# SchemaAction.net
KiCad netlist of a schematic drawn in Altium Designer
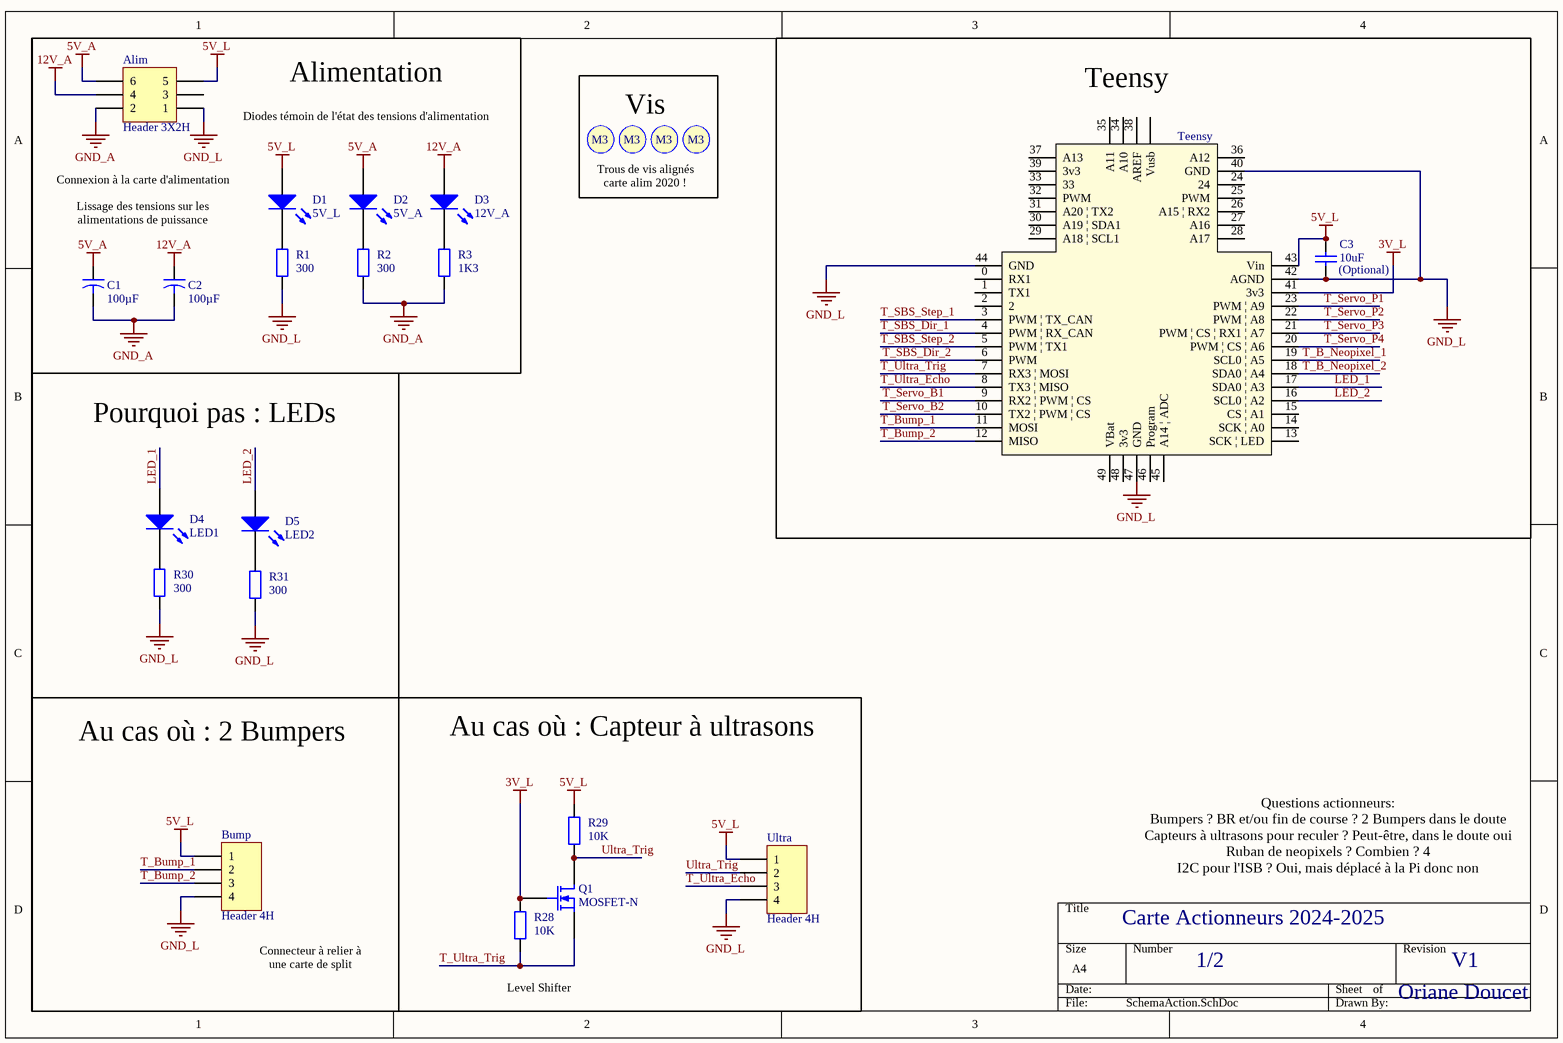
[diagram p0: SchemaAction.SchDoc]

(export (version "E")
  (design (tool "Eeschema 10.0.6"))
  (components
    (comp (ref "Alim")
      (value "Header 3X2H")
      (footprint "MOLEX_MINIFITJR_3X2")
      (description "Header, 3-Pin, Dual row, Right Angle")
      (fields (field (name "PUBLISHER") "Altium Limited"))
      (libsource (lib "Miscellaneous Connectors") (part "Header 3X2H"))
    )
    (comp (ref "Bump")
      (value "Header 4H")
      (footprint "S4B-XH-A")
      (description "Header, 4-Pin, Right Angle")
      (fields (field (name "PUBLISHER") "Altium Limited"))
      (libsource (lib "Miscellaneous Connectors") (part "Header 4H"))
    )
    (comp (ref "C1")
      (value "100µF")
      (footprint "Condensateur")
      (description "Capacitor")
      (fields (field (name "Comment") "Cap2") (field (name "PUBLISHER") "Altium Limited"))
      (libsource (lib "Miscellaneous Devices") (part "Cap2"))
    )
    (comp (ref "C2")
      (value "100µF")
      (footprint "Condensateur")
      (description "Capacitor")
      (fields (field (name "Comment") "Cap2") (field (name "PUBLISHER") "Altium Limited"))
      (libsource (lib "Miscellaneous Devices") (part "Cap2"))
    )
    (comp (ref "C3")
      (value "(Optional)")
      (footprint "Capacitor 1206")
      (description "Capacitor")
      (fields (field (name "ALTIUM_VALUE") "10uF") (field (name "PUBLISHER") "Altium Limited"))
      (libsource (lib "Miscellaneous Devices") (part "Cap"))
    )
    (comp (ref "D1")
      (value "5V_L")
      (footprint "KP-3216SEC")
      (description "Typical RED, GREEN, YELLOW, AMBER GaAs LED")
      (fields (field (name "PUBLISHER") "Altium Limited"))
      (libsource (lib "Miscellaneous Devices") (part "LED2"))
    )
    (comp (ref "D2")
      (value "5V_A")
      (footprint "KP-3216SEC")
      (description "Typical RED, GREEN, YELLOW, AMBER GaAs LED")
      (fields (field (name "PUBLISHER") "Altium Limited"))
      (libsource (lib "Miscellaneous Devices") (part "LED2"))
    )
    (comp (ref "D3")
      (value "12V_A")
      (footprint "KP-3216SEC")
      (description "Typical RED, GREEN, YELLOW, AMBER GaAs LED")
      (fields (field (name "PUBLISHER") "Altium Limited"))
      (libsource (lib "Miscellaneous Devices") (part "LED2"))
    )
    (comp (ref "D4")
      (value "LED1")
      (footprint "KP-3216SEC")
      (description "Typical RED, GREEN, YELLOW, AMBER GaAs LED")
      (fields (field (name "PUBLISHER") "Altium Limited"))
      (libsource (lib "Miscellaneous Devices") (part "LED2"))
    )
    (comp (ref "D5")
      (value "LED2")
      (footprint "KP-3216SEC")
      (description "Typical RED, GREEN, YELLOW, AMBER GaAs LED")
      (fields (field (name "PUBLISHER") "Altium Limited"))
      (libsource (lib "Miscellaneous Devices") (part "LED2"))
    )
    (comp (ref "Q1")
      (value "MOSFET-N")
      (footprint "SOT23_M")
      (description "N-Channel MOSFET")
      (fields (field (name "PUBLISHER") "Altium Limited"))
      (libsource (lib "Miscellaneous Devices") (part "MOSFET-N"))
    )
    (comp (ref "R1")
      (value "300")
      (footprint "Resistor 1206")
      (description "Resistor")
      (fields (field (name "Comment") "Res2") (field (name "PUBLISHER") "Altium Limited"))
      (libsource (lib "") (part "Res2_1"))
    )
    (comp (ref "R2")
      (value "300")
      (footprint "Resistor 1206")
      (description "Resistor")
      (fields (field (name "Comment") "Res2") (field (name "PUBLISHER") "Altium Limited"))
      (libsource (lib "Miscellaneous Devices") (part "Res2"))
    )
    (comp (ref "R3")
      (value "1K3")
      (footprint "Resistor 1206")
      (description "Resistor")
      (fields (field (name "Comment") "Res2") (field (name "PUBLISHER") "Altium Limited"))
      (libsource (lib "Miscellaneous Devices") (part "Res2"))
    )
    (comp (ref "R28")
      (value "10K")
      (footprint "Resistor 1206")
      (description "Resistor")
      (fields (field (name "Comment") "Res2") (field (name "PUBLISHER") "Altium Limited"))
      (libsource (lib "Miscellaneous Devices") (part "Res2"))
    )
    (comp (ref "R29")
      (value "10K")
      (footprint "Resistor 1206")
      (description "Resistor")
      (fields (field (name "Comment") "Res2") (field (name "PUBLISHER") "Altium Limited"))
      (libsource (lib "Miscellaneous Devices") (part "Res2"))
    )
    (comp (ref "R30")
      (value "300")
      (footprint "Resistor 1206")
      (description "Resistor")
      (fields (field (name "Comment") "Res2") (field (name "PUBLISHER") "Altium Limited"))
      (libsource (lib "") (part "Res2_1"))
    )
    (comp (ref "R31")
      (value "300")
      (footprint "Resistor 1206")
      (description "Resistor")
      (fields (field (name "Comment") "Res2") (field (name "PUBLISHER") "Altium Limited"))
      (libsource (lib "") (part "Res2_1"))
    )
    (comp (ref "S1")
      (value "Screw M3")
      (footprint "Screw M3")
      (libsource (lib "Robot_2019") (part "Screw M3"))
    )
    (comp (ref "S2")
      (value "Screw M3")
      (footprint "Screw M3")
      (libsource (lib "Robot_2019") (part "Screw M3"))
    )
    (comp (ref "S3")
      (value "Screw M3")
      (footprint "Screw M3")
      (libsource (lib "Robot_2019") (part "Screw M3"))
    )
    (comp (ref "S4")
      (value "Screw M3")
      (footprint "Screw M3")
      (libsource (lib "Robot_2019") (part "Screw M3"))
    )
    (comp (ref "Teensy")
      (value "Teensy 3.2")
      (footprint "teensy")
      (libsource (lib "Robot_2020") (part "teensy3.2"))
    )
    (comp (ref "Ultra")
      (value "Header 4H")
      (footprint "S4B-XH-A")
      (description "Header, 4-Pin, Right Angle")
      (fields (field (name "PUBLISHER") "Altium Limited"))
      (libsource (lib "Miscellaneous Connectors") (part "Header 4H"))
    )
  )
  (nets
    (net (code "1") (name "/LED_1") (class "Default")
      (node (ref "D4") (pin "1") (pinfunction "A_1") (pintype "passive"))
      (node (ref "Teensy") (pin "17") (pinfunction "SDA0_¦_A3_17") (pintype "passive"))
    )
    (net (code "2") (name "/LED_2") (class "Default")
      (node (ref "D5") (pin "1") (pinfunction "A_1") (pintype "passive"))
      (node (ref "Teensy") (pin "16") (pinfunction "SCL0_¦_A2_16") (pintype "passive"))
    )
    (net (code "3") (name "/T_B_Neopixel_1") (class "Default")
      (node (ref "Teensy") (pin "19") (pinfunction "SCL0_¦_A5_19") (pintype "passive"))
    )
    (net (code "4") (name "/T_B_Neopixel_2") (class "Default")
      (node (ref "Teensy") (pin "18") (pinfunction "SDA0_¦_A4_18") (pintype "passive"))
    )
    (net (code "5") (name "/T_Bump_1") (class "Default")
      (node (ref "Bump") (pin "2") (pinfunction "2_2") (pintype "passive"))
      (node (ref "Teensy") (pin "11") (pinfunction "MOSI_11") (pintype "passive"))
    )
    (net (code "6") (name "/T_Bump_2") (class "Default")
      (node (ref "Bump") (pin "3") (pinfunction "3_3") (pintype "passive"))
      (node (ref "Teensy") (pin "12") (pinfunction "MISO_12") (pintype "passive"))
    )
    (net (code "7") (name "/T_SBS_Dir_1") (class "Default")
      (node (ref "Teensy") (pin "4") (pinfunction "PWM_¦_RX_CAN_4") (pintype "passive"))
    )
    (net (code "8") (name "/T_SBS_Dir_2") (class "Default")
      (node (ref "Teensy") (pin "6") (pinfunction "PWM_6") (pintype "passive"))
    )
    (net (code "9") (name "/T_SBS_Step_1") (class "Default")
      (node (ref "Teensy") (pin "3") (pinfunction "PWM_¦_TX_CAN_3") (pintype "passive"))
    )
    (net (code "10") (name "/T_SBS_Step_2") (class "Default")
      (node (ref "Teensy") (pin "5") (pinfunction "PWM_¦_TX1_5") (pintype "passive"))
    )
    (net (code "11") (name "/T_Servo_B1") (class "Default")
      (node (ref "Teensy") (pin "9") (pinfunction "RX2_¦_PWM_¦_CS_9") (pintype "passive"))
    )
    (net (code "12") (name "/T_Servo_B2") (class "Default")
      (node (ref "Teensy") (pin "10") (pinfunction "TX2_¦_PWM_¦_CS_10") (pintype "passive"))
    )
    (net (code "13") (name "/T_Servo_P1") (class "Default")
      (node (ref "Teensy") (pin "23") (pinfunction "PWM_¦_A9_23") (pintype "passive"))
    )
    (net (code "14") (name "/T_Servo_P2") (class "Default")
      (node (ref "Teensy") (pin "22") (pinfunction "PWM_¦_A8_22") (pintype "passive"))
    )
    (net (code "15") (name "/T_Servo_P3") (class "Default")
      (node (ref "Teensy") (pin "21") (pinfunction "PWM_¦_CS_¦_RX1_¦_A7_21") (pintype "passive"))
    )
    (net (code "16") (name "/T_Servo_P4") (class "Default")
      (node (ref "Teensy") (pin "20") (pinfunction "PWM_¦_CS_¦_A6_20") (pintype "passive"))
    )
    (net (code "17") (name "/T_Ultra_Echo") (class "Default")
      (node (ref "Teensy") (pin "8") (pinfunction "TX3_¦_MISO_8") (pintype "passive"))
      (node (ref "Ultra") (pin "3") (pinfunction "3_3") (pintype "passive"))
    )
    (net (code "18") (name "/T_Ultra_Trig") (class "Default")
      (node (ref "Q1") (pin "3") (pinfunction "S_3") (pintype "passive"))
      (node (ref "R28") (pin "2") (pinfunction "2_2") (pintype "passive"))
      (node (ref "Teensy") (pin "7") (pinfunction "RX3_¦_MOSI_7") (pintype "passive"))
    )
    (net (code "19") (name "/Ultra_Trig") (class "Default")
      (node (ref "Q1") (pin "1") (pinfunction "D_1") (pintype "passive"))
      (node (ref "R29") (pin "2") (pinfunction "2_2") (pintype "passive"))
      (node (ref "Ultra") (pin "2") (pinfunction "2_2") (pintype "passive"))
    )
    (net (code "20") (name "3V_L") (class "Default")
      (node (ref "Q1") (pin "2") (pinfunction "G_2") (pintype "passive"))
      (node (ref "R28") (pin "1") (pinfunction "1_1") (pintype "passive"))
      (node (ref "Teensy") (pin "41") (pinfunction "3v3_41") (pintype "passive"))
    )
    (net (code "21") (name "5V_A") (class "Default")
      (node (ref "Alim") (pin "6") (pinfunction "6_6") (pintype "passive"))
      (node (ref "C1") (pin "1") (pinfunction "1_1") (pintype "passive"))
      (node (ref "D2") (pin "1") (pinfunction "A_1") (pintype "passive"))
    )
    (net (code "22") (name "5V_L") (class "Default")
      (node (ref "Alim") (pin "5") (pinfunction "5_5") (pintype "passive"))
      (node (ref "Bump") (pin "1") (pinfunction "1_1") (pintype "passive"))
      (node (ref "C3") (pin "2") (pinfunction "2_2") (pintype "passive"))
      (node (ref "D1") (pin "1") (pinfunction "A_1") (pintype "passive"))
      (node (ref "R29") (pin "1") (pinfunction "1_1") (pintype "passive"))
      (node (ref "Teensy") (pin "43") (pinfunction "Vin_43") (pintype "passive"))
      (node (ref "Ultra") (pin "1") (pinfunction "1_1") (pintype "passive"))
    )
    (net (code "23") (name "12V_A") (class "Default")
      (node (ref "Alim") (pin "4") (pinfunction "4_4") (pintype "passive"))
      (node (ref "C2") (pin "1") (pinfunction "1_1") (pintype "passive"))
      (node (ref "D3") (pin "1") (pinfunction "A_1") (pintype "passive"))
    )
    (net (code "24") (name "GND_A") (class "Default")
      (node (ref "Alim") (pin "2") (pinfunction "2_2") (pintype "passive"))
      (node (ref "C1") (pin "2") (pinfunction "2_2") (pintype "passive"))
      (node (ref "C2") (pin "2") (pinfunction "2_2") (pintype "passive"))
      (node (ref "R2") (pin "2") (pinfunction "2_2") (pintype "passive"))
      (node (ref "R3") (pin "2") (pinfunction "2_2") (pintype "passive"))
    )
    (net (code "25") (name "GND_L") (class "Default")
      (node (ref "Alim") (pin "1") (pinfunction "1_1") (pintype "passive"))
      (node (ref "Bump") (pin "4") (pinfunction "4_4") (pintype "passive"))
      (node (ref "C3") (pin "1") (pinfunction "1_1") (pintype "passive"))
      (node (ref "R1") (pin "1") (pinfunction "1_1") (pintype "passive"))
      (node (ref "R30") (pin "1") (pinfunction "1_1") (pintype "passive"))
      (node (ref "R31") (pin "1") (pinfunction "1_1") (pintype "passive"))
      (node (ref "Teensy") (pin "40") (pinfunction "GND_40") (pintype "passive"))
      (node (ref "Teensy") (pin "42") (pinfunction "AGND_42") (pintype "passive"))
      (node (ref "Teensy") (pin "44") (pinfunction "GND_44") (pintype "passive"))
      (node (ref "Teensy") (pin "47") (pinfunction "GND_47") (pintype "passive"))
      (node (ref "Ultra") (pin "4") (pinfunction "4_4") (pintype "passive"))
    )
    (net (code "26") (name "Net-(D1-K)") (class "Default")
      (node (ref "D1") (pin "2") (pinfunction "K_2") (pintype "passive"))
      (node (ref "R1") (pin "2") (pinfunction "2_2") (pintype "passive"))
    )
    (net (code "27") (name "Net-(D2-K)") (class "Default")
      (node (ref "D2") (pin "2") (pinfunction "K_2") (pintype "passive"))
      (node (ref "R2") (pin "1") (pinfunction "1_1") (pintype "passive"))
    )
    (net (code "28") (name "Net-(D3-K)") (class "Default")
      (node (ref "D3") (pin "2") (pinfunction "K_2") (pintype "passive"))
      (node (ref "R3") (pin "1") (pinfunction "1_1") (pintype "passive"))
    )
    (net (code "29") (name "Net-(D4-K)") (class "Default")
      (node (ref "D4") (pin "2") (pinfunction "K_2") (pintype "passive"))
      (node (ref "R30") (pin "2") (pinfunction "2_2") (pintype "passive"))
    )
    (net (code "30") (name "Net-(D5-K)") (class "Default")
      (node (ref "D5") (pin "2") (pinfunction "K_2") (pintype "passive"))
      (node (ref "R31") (pin "2") (pinfunction "2_2") (pintype "passive"))
    )
    (net (code "31") (name "unconnected-(Alim-Pad3)") (class "Default")
      (node (ref "Alim") (pin "3") (pinfunction "3_3") (pintype "passive"))
    )
    (net (code "32") (name "unconnected-(Teensy-3v3-Pad39)") (class "Default")
      (node (ref "Teensy") (pin "39") (pinfunction "3v3_39") (pintype "passive"))
    )
    (net (code "33") (name "unconnected-(Teensy-3v3-Pad48)") (class "Default")
      (node (ref "Teensy") (pin "48") (pinfunction "3v3_48") (pintype "passive"))
    )
    (net (code "34") (name "unconnected-(Teensy-A10-Pad34)") (class "Default")
      (node (ref "Teensy") (pin "34") (pinfunction "A10_34") (pintype "passive"))
    )
    (net (code "35") (name "unconnected-(Teensy-A11-Pad35)") (class "Default")
      (node (ref "Teensy") (pin "35") (pinfunction "A11_35") (pintype "passive"))
    )
    (net (code "36") (name "unconnected-(Teensy-A12-Pad36)") (class "Default")
      (node (ref "Teensy") (pin "36") (pinfunction "A12_36") (pintype "passive"))
    )
    (net (code "37") (name "unconnected-(Teensy-A13-Pad37)") (class "Default")
      (node (ref "Teensy") (pin "37") (pinfunction "A13_37") (pintype "passive"))
    )
    (net (code "38") (name "unconnected-(Teensy-A14_¦_ADC-Pad45)") (class "Default")
      (node (ref "Teensy") (pin "45") (pinfunction "A14_¦_ADC_45") (pintype "passive"))
    )
    (net (code "39") (name "unconnected-(Teensy-A15_¦_RX2-Pad26)") (class "Default")
      (node (ref "Teensy") (pin "26") (pinfunction "A15_¦_RX2_26") (pintype "passive"))
    )
    (net (code "40") (name "unconnected-(Teensy-A16-Pad27)") (class "Default")
      (node (ref "Teensy") (pin "27") (pinfunction "A16_27") (pintype "passive"))
    )
    (net (code "41") (name "unconnected-(Teensy-A17-Pad28)") (class "Default")
      (node (ref "Teensy") (pin "28") (pinfunction "A17_28") (pintype "passive"))
    )
    (net (code "42") (name "unconnected-(Teensy-A18_¦_SCL1-Pad29)") (class "Default")
      (node (ref "Teensy") (pin "29") (pinfunction "A18_¦_SCL1_29") (pintype "passive"))
    )
    (net (code "43") (name "unconnected-(Teensy-A19_¦_SDA1-Pad30)") (class "Default")
      (node (ref "Teensy") (pin "30") (pinfunction "A19_¦_SDA1_30") (pintype "passive"))
    )
    (net (code "44") (name "unconnected-(Teensy-A20_¦_TX2-Pad31)") (class "Default")
      (node (ref "Teensy") (pin "31") (pinfunction "A20_¦_TX2_31") (pintype "passive"))
    )
    (net (code "45") (name "unconnected-(Teensy-AREF-Pad38)") (class "Default")
      (node (ref "Teensy") (pin "38") (pinfunction "AREF_38") (pintype "passive"))
    )
    (net (code "46") (name "unconnected-(Teensy-CS_¦_A1-Pad15)") (class "Default")
      (node (ref "Teensy") (pin "15") (pinfunction "CS_¦_A1_15") (pintype "passive"))
    )
    (net (code "47") (name "unconnected-(Teensy-PWM-Pad25)") (class "Default")
      (node (ref "Teensy") (pin "25") (pinfunction "PWM_25") (pintype "passive"))
    )
    (net (code "48") (name "unconnected-(Teensy-PWM-Pad32)") (class "Default")
      (node (ref "Teensy") (pin "32") (pinfunction "PWM_32") (pintype "passive"))
    )
    (net (code "49") (name "unconnected-(Teensy-Pad2)") (class "Default")
      (node (ref "Teensy") (pin "2") (pinfunction "2_2") (pintype "passive"))
    )
    (net (code "50") (name "unconnected-(Teensy-Pad24)") (class "Default")
      (node (ref "Teensy") (pin "24") (pinfunction "24_24") (pintype "passive"))
    )
    (net (code "51") (name "unconnected-(Teensy-Pad33)") (class "Default")
      (node (ref "Teensy") (pin "33") (pinfunction "33_33") (pintype "passive"))
    )
    (net (code "52") (name "unconnected-(Teensy-Program-Pad46)") (class "Default")
      (node (ref "Teensy") (pin "46") (pinfunction "Program_46") (pintype "passive"))
    )
    (net (code "53") (name "unconnected-(Teensy-RX1-Pad0)") (class "Default")
      (node (ref "Teensy") (pin "0") (pinfunction "RX1_0") (pintype "passive"))
    )
    (net (code "54") (name "unconnected-(Teensy-SCK_¦_A0-Pad14)") (class "Default")
      (node (ref "Teensy") (pin "14") (pinfunction "SCK_¦_A0_14") (pintype "passive"))
    )
    (net (code "55") (name "unconnected-(Teensy-SCK_¦_LED-Pad13)") (class "Default")
      (node (ref "Teensy") (pin "13") (pinfunction "SCK_¦_LED_13") (pintype "passive"))
    )
    (net (code "56") (name "unconnected-(Teensy-TX1-Pad1)") (class "Default")
      (node (ref "Teensy") (pin "1") (pinfunction "TX1_1") (pintype "passive"))
    )
    (net (code "57") (name "unconnected-(Teensy-VBat-Pad49)") (class "Default")
      (node (ref "Teensy") (pin "49") (pinfunction "VBat_49") (pintype "passive"))
    )
    (net (code "58") (name "unconnected-(Teensy-Vusb-Pad50)") (class "Default")
      (node (ref "Teensy") (pin "50") (pinfunction "Vusb_50") (pintype "passive"))
    )
  )
)
